# quadcopter.net
KiCad netlist of a schematic drawn in EAGLE
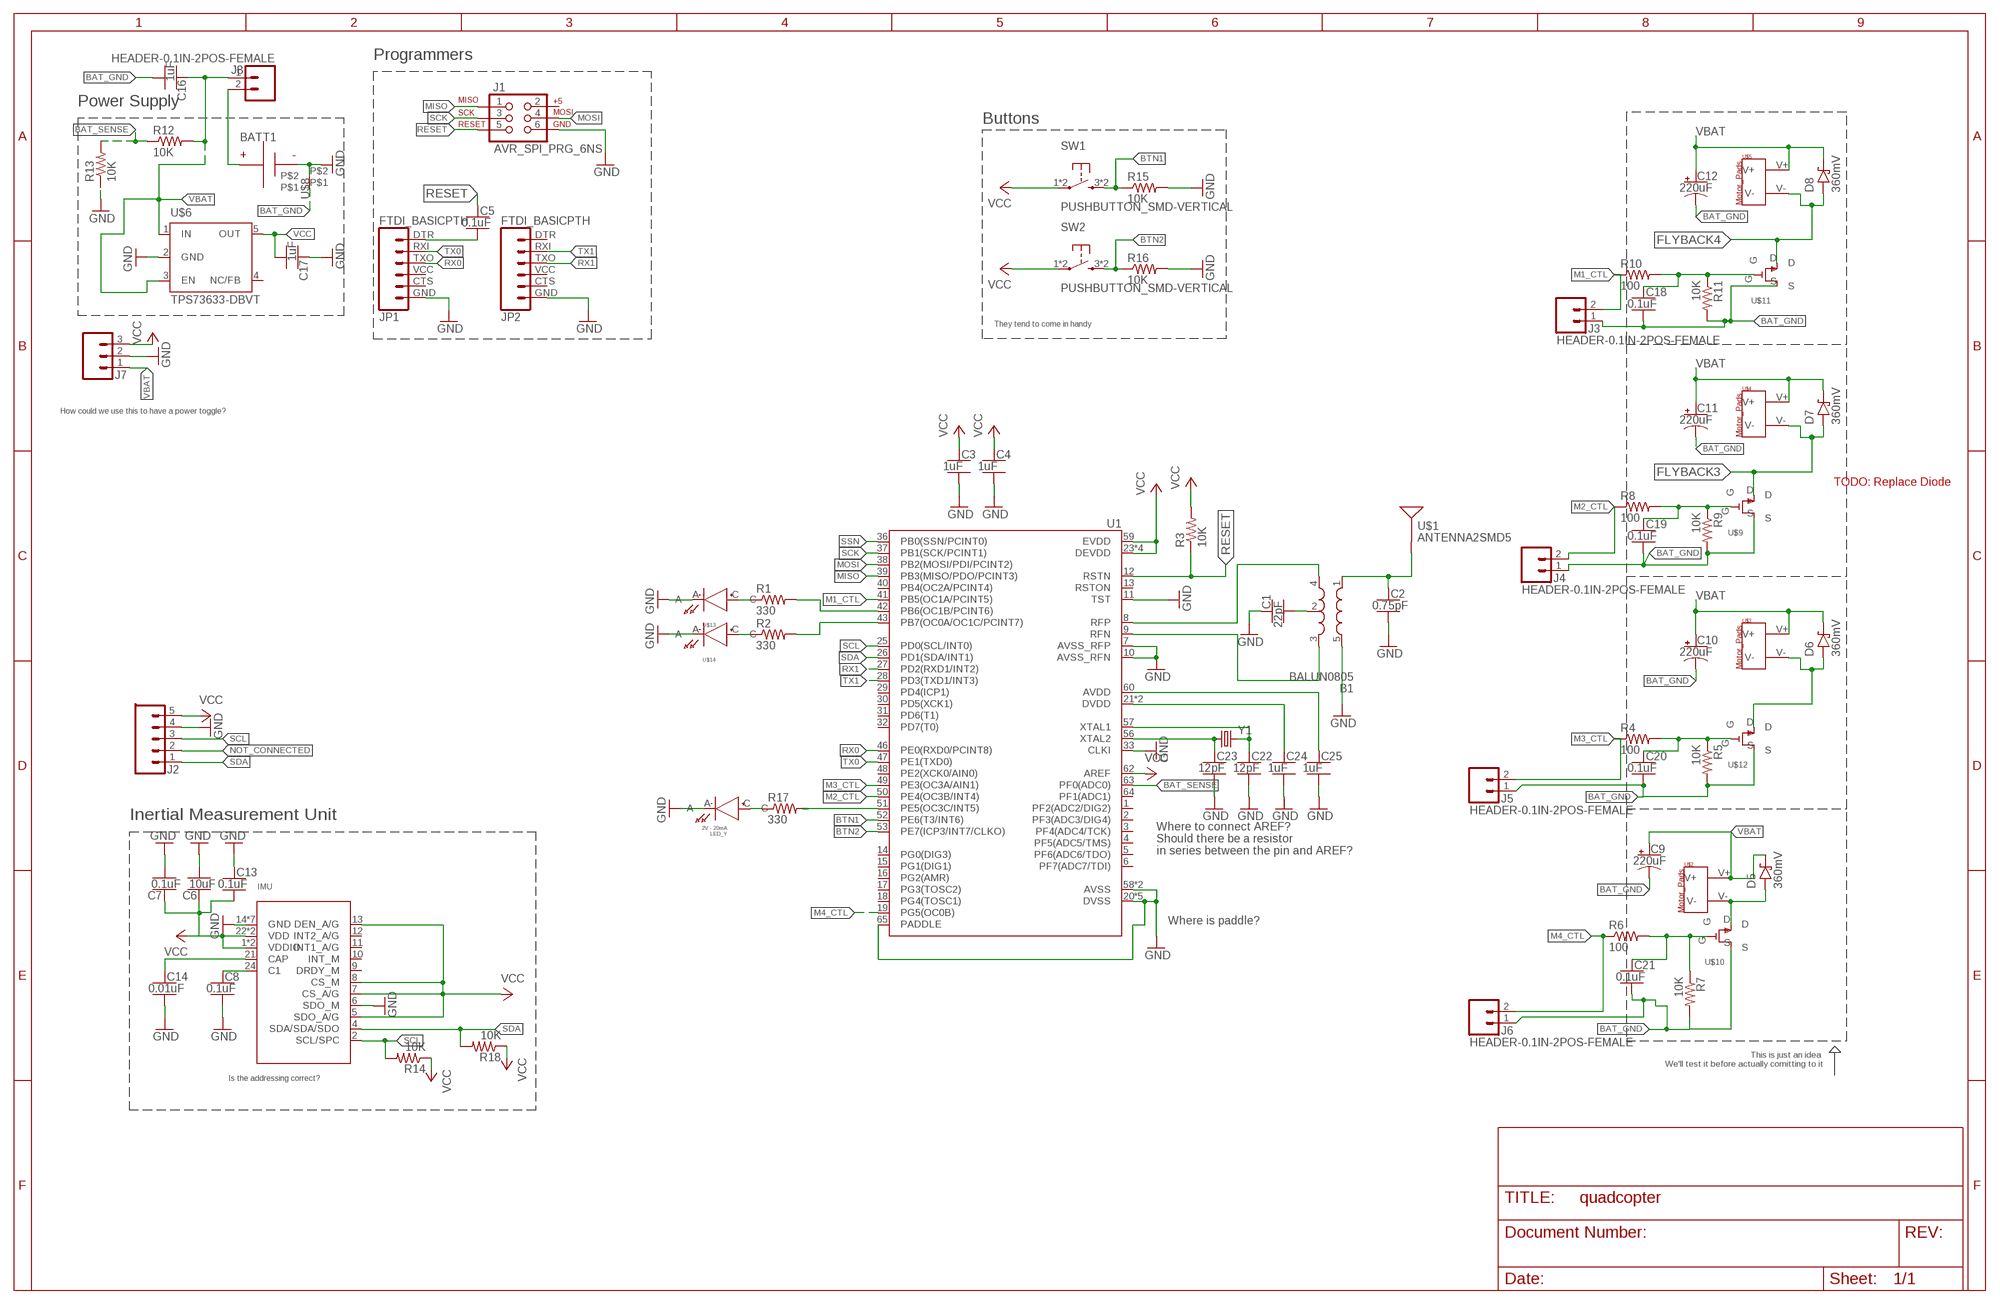
[diagram p0: schematic, sheet 1]

(export (version "E")
  (design (tool "Eeschema 10.0.6"))
  (components
    (comp (ref "B1")
      (value "BALUN0805")
      (footprint "eagle-import:BALUN")
      (fields (field (name "MFR") "Wurth Electronics Inc") (field (name "MPN") "748421245"))
      (libsource (lib "eagle-import") (part "BALUN0805"))
    )
    (comp (ref "BATT1")
      (value "BATTERY-HUBSAN-W/HOLDER")
      (footprint "eagle-import:BATTERY-W_HOLDER-380MAH-HUBSAN")
      (fields
        (field (name "MFR") "HUBSAN")
        (field (name "MPN") "X4-H107C-8-in-1")
        (field (name "CREATOR") "Swanson")
      )
      (libsource (lib "eagle-import") (part "BATTERY-HUBSAN-W/HOLDER"))
    )
    (comp (ref "C1")
      (value "22pF")
      (footprint "eagle-import:CAPC2012X140_HS")
      (fields
        (field (name "MFR") "Murata Electronics North America")
        (field (name "MPN") "GRM21A5C2E220JW01D")
      )
      (libsource (lib "eagle-import") (part "CAPACITOR-NP_SMD-2012-0805_CERAMIC-22PF"))
    )
    (comp (ref "C2")
      (value "0.75pF")
      (footprint "eagle-import:CAPC2012X140_HS")
      (fields
        (field (name "MFR") "Murata Electronics North America")
        (field (name "MPN") "GQM2195C2AR75CB01D")
      )
      (libsource (lib "eagle-import") (part "CAPACITOR-NP_SMD-2012-0805_CERAMIC-0.75PF"))
    )
    (comp (ref "C3")
      (value "1uF")
      (footprint "eagle-import:CAPC2012X140_HS")
      (fields
        (field (name "MFR") "Murata Electronics North America")
        (field (name "MPN") "GRM21BR71H105KA12L")
      )
      (libsource (lib "eagle-import") (part "CAPACITOR-NP_SMD-2012-0805_CERAMIC-1UF"))
    )
    (comp (ref "C4")
      (value "1uF")
      (footprint "eagle-import:CAPC2012X140_HS")
      (fields
        (field (name "MFR") "Murata Electronics North America")
        (field (name "MPN") "GRM21BR71H105KA12L")
      )
      (libsource (lib "eagle-import") (part "CAPACITOR-NP_SMD-2012-0805_CERAMIC-1UF"))
    )
    (comp (ref "C5")
      (value "0.1uF")
      (footprint "eagle-import:CAPC2012X140_HS")
      (fields
        (field (name "MFR") "Murata Electronics North America")
        (field (name "MPN") "GRM21BR71H104KA01L")
      )
      (libsource (lib "eagle-import") (part "CAPACITOR-NP_SMD-2012-0805_CERAMIC-0.1UF"))
    )
    (comp (ref "C6")
      (value "10uF")
      (footprint "eagle-import:CAPC2012X140_HS")
      (fields
        (field (name "MFR") "Murata Electronics North America")
        (field (name "MPN") "GRM21BR61E106KA73L")
      )
      (libsource (lib "eagle-import") (part "CAPACITOR-NP_SMD-2012-0805_CERAMIC-10UF"))
    )
    (comp (ref "C7")
      (value "0.1uF")
      (footprint "eagle-import:CAPC2012X140_HS")
      (fields
        (field (name "MFR") "Murata Electronics North America")
        (field (name "MPN") "GRM21BR71H104KA01L")
      )
      (libsource (lib "eagle-import") (part "CAPACITOR-NP_SMD-2012-0805_CERAMIC-0.1UF"))
    )
    (comp (ref "C8")
      (value "0.1uF")
      (footprint "eagle-import:CAPC2012X140_HS")
      (fields
        (field (name "MFR") "Murata Electronics North America")
        (field (name "MPN") "GRM21BR71H104KA01L")
      )
      (libsource (lib "eagle-import") (part "CAPACITOR-NP_SMD-2012-0805_CERAMIC-0.1UF"))
    )
    (comp (ref "C9")
      (value "220uF")
      (footprint "eagle-import:CAPMP7343X310_HS")
      (fields (field (name "MFR") "AVX Corporation") (field (name "MPN") "TAJD227K006RNJ"))
      (libsource (lib "eagle-import") (part "CAPACITOR-POL_SMD-7043-D_TANTALUM-220UF"))
    )
    (comp (ref "C10")
      (value "220uF")
      (footprint "eagle-import:CAPMP7343X310_HS")
      (fields (field (name "MFR") "AVX Corporation") (field (name "MPN") "TAJD227K006RNJ"))
      (libsource (lib "eagle-import") (part "CAPACITOR-POL_SMD-7043-D_TANTALUM-220UF"))
    )
    (comp (ref "C11")
      (value "220uF")
      (footprint "eagle-import:CAPMP7343X310_HS")
      (fields (field (name "MFR") "AVX Corporation") (field (name "MPN") "TAJD227K006RNJ"))
      (libsource (lib "eagle-import") (part "CAPACITOR-POL_SMD-7043-D_TANTALUM-220UF"))
    )
    (comp (ref "C12")
      (value "220uF")
      (footprint "eagle-import:CAPMP7343X310_HS")
      (fields (field (name "MFR") "AVX Corporation") (field (name "MPN") "TAJD227K006RNJ"))
      (libsource (lib "eagle-import") (part "CAPACITOR-POL_SMD-7043-D_TANTALUM-220UF"))
    )
    (comp (ref "C13")
      (value "0.1uF")
      (footprint "eagle-import:CAPC2012X140_HS")
      (fields
        (field (name "MFR") "Murata Electronics North America")
        (field (name "MPN") "GRM21BR71H104KA01L")
      )
      (libsource (lib "eagle-import") (part "CAPACITOR-NP_SMD-2012-0805_CERAMIC-0.1UF"))
    )
    (comp (ref "C14")
      (value "0.01uF")
      (footprint "eagle-import:CAPC2012X140_HS")
      (fields
        (field (name "MFR") "Murata Electronics North America")
        (field (name "MPN") "GRM2195C1H103FA01D")
      )
      (libsource (lib "eagle-import") (part "CAPACITOR-NP_SMD-2012-0805_CERAMIC-0.01UF"))
    )
    (comp (ref "C16")
      (value "1uF")
      (footprint "eagle-import:CAPC2012X140_HS")
      (fields
        (field (name "MFR") "Murata Electronics North America")
        (field (name "MPN") "GRM21BR71H105KA12L")
      )
      (libsource (lib "eagle-import") (part "CAPACITOR-NP_SMD-2012-0805_CERAMIC-1UF"))
    )
    (comp (ref "C17")
      (value "1uF")
      (footprint "eagle-import:CAPC2012X140_HS")
      (fields
        (field (name "MFR") "Murata Electronics North America")
        (field (name "MPN") "GRM21BR71H105KA12L")
      )
      (libsource (lib "eagle-import") (part "CAPACITOR-NP_SMD-2012-0805_CERAMIC-1UF"))
    )
    (comp (ref "C18")
      (value "0.1uF")
      (footprint "eagle-import:CAPC2012X140_HS")
      (fields
        (field (name "MFR") "Murata Electronics North America")
        (field (name "MPN") "GRM21BR71H104KA01L")
      )
      (libsource (lib "eagle-import") (part "CAPACITOR-NP_SMD-2012-0805_CERAMIC-0.1UF"))
    )
    (comp (ref "C19")
      (value "0.1uF")
      (footprint "eagle-import:CAPC2012X140_HS")
      (fields
        (field (name "MFR") "Murata Electronics North America")
        (field (name "MPN") "GRM21BR71H104KA01L")
      )
      (libsource (lib "eagle-import") (part "CAPACITOR-NP_SMD-2012-0805_CERAMIC-0.1UF"))
    )
    (comp (ref "C20")
      (value "0.1uF")
      (footprint "eagle-import:CAPC2012X140_HS")
      (fields
        (field (name "MFR") "Murata Electronics North America")
        (field (name "MPN") "GRM21BR71H104KA01L")
      )
      (libsource (lib "eagle-import") (part "CAPACITOR-NP_SMD-2012-0805_CERAMIC-0.1UF"))
    )
    (comp (ref "C21")
      (value "0.1uF")
      (footprint "eagle-import:CAPC2012X140_HS")
      (fields
        (field (name "MFR") "Murata Electronics North America")
        (field (name "MPN") "GRM21BR71H104KA01L")
      )
      (libsource (lib "eagle-import") (part "CAPACITOR-NP_SMD-2012-0805_CERAMIC-0.1UF"))
    )
    (comp (ref "C22")
      (value "12pF")
      (footprint "eagle-import:CAPC2012X140_HS")
      (fields
        (field (name "MFR") "Murata Electronics North America")
        (field (name "MPN") "GRM21A5C2E120JW01D")
      )
      (libsource (lib "eagle-import") (part "CAPACITOR-NP_SMD-2012-0805_CERAMIC-12PF"))
    )
    (comp (ref "C23")
      (value "12pF")
      (footprint "eagle-import:CAPC2012X140_HS")
      (fields
        (field (name "MFR") "Murata Electronics North America")
        (field (name "MPN") "GRM21A5C2E120JW01D")
      )
      (libsource (lib "eagle-import") (part "CAPACITOR-NP_SMD-2012-0805_CERAMIC-12PF"))
    )
    (comp (ref "C24")
      (value "1uF")
      (footprint "eagle-import:CAPC2012X140_HS")
      (fields
        (field (name "MFR") "Murata Electronics North America")
        (field (name "MPN") "GRM21BR71H105KA12L")
      )
      (libsource (lib "eagle-import") (part "CAPACITOR-NP_SMD-2012-0805_CERAMIC-1UF"))
    )
    (comp (ref "C25")
      (value "1uF")
      (footprint "eagle-import:CAPC2012X140_HS")
      (fields
        (field (name "MFR") "Murata Electronics North America")
        (field (name "MPN") "GRM21BR71H105KA12L")
      )
      (libsource (lib "eagle-import") (part "CAPACITOR-NP_SMD-2012-0805_CERAMIC-1UF"))
    )
    (comp (ref "D5")
      (value "360mV")
      (footprint "eagle-import:SOD3716X135_HS")
      (fields
        (field (name "MFR") "Toshiba Semiconductor and Storage")
        (field (name "MPN") "CRS08(TE85L,Q,M)")
      )
      (libsource (lib "eagle-import") (part "DIODE-SCHOTTKY_SMD-SOD123-360MV"))
    )
    (comp (ref "D6")
      (value "360mV")
      (footprint "eagle-import:SOD3716X135_HS")
      (fields
        (field (name "MFR") "Toshiba Semiconductor and Storage")
        (field (name "MPN") "CRS08(TE85L,Q,M)")
      )
      (libsource (lib "eagle-import") (part "DIODE-SCHOTTKY_SMD-SOD123-360MV"))
    )
    (comp (ref "D7")
      (value "360mV")
      (footprint "eagle-import:SOD3716X135_HS")
      (fields
        (field (name "MFR") "Toshiba Semiconductor and Storage")
        (field (name "MPN") "CRS08(TE85L,Q,M)")
      )
      (libsource (lib "eagle-import") (part "DIODE-SCHOTTKY_SMD-SOD123-360MV"))
    )
    (comp (ref "D8")
      (value "360mV")
      (footprint "eagle-import:SOD3716X135_HS")
      (fields
        (field (name "MFR") "Toshiba Semiconductor and Storage")
        (field (name "MPN") "CRS08(TE85L,Q,M)")
      )
      (libsource (lib "eagle-import") (part "DIODE-SCHOTTKY_SMD-SOD123-360MV"))
    )
    (comp (ref "IMU")
      (value "IMU")
      (footprint "eagle-import:IMU_LSM9DS1TR")
      (fields
        (field (name "MFR") "STMicroelectronics ")
        (field (name "MPN") "LSM9DS1TR ")
        (field (name "CREATOR") "Michael M. Gonzalez")
      )
      (libsource (lib "eagle-import") (part "IMU"))
    )
    (comp (ref "J1")
      (value "AVR_SPI_PRG_6NS")
      (footprint "eagle-import:2X3-NS")
      (fields (field (name "MFR") "Amphenol FCI") (field (name "MPN") "67997-206HLF"))
      (libsource (lib "eagle-import") (part "AVR_SPI_PRG_6NS"))
    )
    (comp (ref "J2")
      (value "HEADER-0.1IN-5POS-FEMALE")
      (footprint "eagle-import:HDRV5W63P254_5X1_1270X254H838_HS")
      (libsource (lib "eagle-import") (part "HEADER-0.1IN-5POS-FEMALE"))
    )
    (comp (ref "J3")
      (value "HEADER-0.1IN-2POS-FEMALE")
      (footprint "eagle-import:HDRV2W63P254_2X1_508X254H838_HS")
      (libsource (lib "eagle-import") (part "HEADER-0.1IN-2POS-FEMALE"))
    )
    (comp (ref "J4")
      (value "HEADER-0.1IN-2POS-FEMALE")
      (footprint "eagle-import:HDRV2W63P254_2X1_508X254H838_HS")
      (libsource (lib "eagle-import") (part "HEADER-0.1IN-2POS-FEMALE"))
    )
    (comp (ref "J5")
      (value "HEADER-0.1IN-2POS-FEMALE")
      (footprint "eagle-import:HDRV2W63P254_2X1_508X254H838_HS")
      (libsource (lib "eagle-import") (part "HEADER-0.1IN-2POS-FEMALE"))
    )
    (comp (ref "J6")
      (value "HEADER-0.1IN-2POS-FEMALE")
      (footprint "eagle-import:HDRV2W63P254_2X1_508X254H838_HS")
      (libsource (lib "eagle-import") (part "HEADER-0.1IN-2POS-FEMALE"))
    )
    (comp (ref "J7")
      (value "HEADER-0.1IN-3POS-MALE")
      (footprint "eagle-import:HDRV3W63P254_3X1_762X254H838_HS")
      (libsource (lib "eagle-import") (part "HEADER-0.1IN-3POS-MALE"))
    )
    (comp (ref "J8")
      (value "HEADER-0.1IN-2POS-FEMALE")
      (footprint "eagle-import:HDRV2W63P254_2X1_508X254H838_HS")
      (libsource (lib "eagle-import") (part "HEADER-0.1IN-2POS-FEMALE"))
    )
    (comp (ref "JP1")
      (value "FTDI_BASICPTH")
      (footprint "eagle-import:FTDI_BASIC")
      (fields (field (name "MFR") "Amphenol FCI") (field (name "MPN") "68016-406HLF"))
      (libsource (lib "eagle-import") (part "FTDI_BASICPTH"))
    )
    (comp (ref "JP2")
      (value "FTDI_BASICPTH")
      (footprint "eagle-import:FTDI_BASIC")
      (fields (field (name "MFR") "Amphenol FCI") (field (name "MPN") "68016-406HLF"))
      (libsource (lib "eagle-import") (part "FTDI_BASICPTH"))
    )
    (comp (ref "LED_Y")
      (value "2V - 20mA")
      (footprint "eagle-import:LED_LTST-C170EKT")
      (fields
        (field (name "MFR") "Visual Communications Company - VCC")
        (field (name "MPN") "CMD17-21VYD/TR8")
        (field (name "CREATOR") "Michael M. Gonzalez")
      )
      (libsource (lib "eagle-import") (part "LEDCMD17"))
    )
    (comp (ref "R1")
      (value "330")
      (footprint "eagle-import:RESC2012X60_HS")
      (fields (field (name "MFR") "Yageo") (field (name "MPN") "RC0805JR-07330RL"))
      (libsource (lib "eagle-import") (part "RESISTOR_SMD-2012-0805-330"))
    )
    (comp (ref "R2")
      (value "330")
      (footprint "eagle-import:RESC2012X60_HS")
      (fields (field (name "MFR") "Yageo") (field (name "MPN") "RC0805JR-07330RL"))
      (libsource (lib "eagle-import") (part "RESISTOR_SMD-2012-0805-330"))
    )
    (comp (ref "R3")
      (value "10K")
      (footprint "eagle-import:RESC2012X60_HS")
      (fields (field (name "MFR") "Yageo") (field (name "MPN") "RC0805JR-0710KL"))
      (libsource (lib "eagle-import") (part "RESISTOR_SMD-2012-0805-10K"))
    )
    (comp (ref "R4")
      (value "100")
      (footprint "eagle-import:RESC2012X60_HS")
      (fields (field (name "MFR") "Yageo") (field (name "MPN") "RC0805JR-07100RL"))
      (libsource (lib "eagle-import") (part "RESISTOR_SMD-2012-0805-100"))
    )
    (comp (ref "R5")
      (value "10K")
      (footprint "eagle-import:RESC2012X60_HS")
      (fields (field (name "MFR") "Yageo") (field (name "MPN") "RC0805JR-0710KL"))
      (libsource (lib "eagle-import") (part "RESISTOR_SMD-2012-0805-10K"))
    )
    (comp (ref "R6")
      (value "100")
      (footprint "eagle-import:RESC2012X60_HS")
      (fields (field (name "MFR") "Yageo") (field (name "MPN") "RC0805JR-07100RL"))
      (libsource (lib "eagle-import") (part "RESISTOR_SMD-2012-0805-100"))
    )
    (comp (ref "R7")
      (value "10K")
      (footprint "eagle-import:RESC2012X60_HS")
      (fields (field (name "MFR") "Yageo") (field (name "MPN") "RC0805JR-0710KL"))
      (libsource (lib "eagle-import") (part "RESISTOR_SMD-2012-0805-10K"))
    )
    (comp (ref "R8")
      (value "100")
      (footprint "eagle-import:RESC2012X60_HS")
      (fields (field (name "MFR") "Yageo") (field (name "MPN") "RC0805JR-07100RL"))
      (libsource (lib "eagle-import") (part "RESISTOR_SMD-2012-0805-100"))
    )
    (comp (ref "R9")
      (value "10K")
      (footprint "eagle-import:RESC2012X60_HS")
      (fields (field (name "MFR") "Yageo") (field (name "MPN") "RC0805JR-0710KL"))
      (libsource (lib "eagle-import") (part "RESISTOR_SMD-2012-0805-10K"))
    )
    (comp (ref "R10")
      (value "100")
      (footprint "eagle-import:RESC2012X60_HS")
      (fields (field (name "MFR") "Yageo") (field (name "MPN") "RC0805JR-07100RL"))
      (libsource (lib "eagle-import") (part "RESISTOR_SMD-2012-0805-100"))
    )
    (comp (ref "R11")
      (value "10K")
      (footprint "eagle-import:RESC2012X60_HS")
      (fields (field (name "MFR") "Yageo") (field (name "MPN") "RC0805JR-0710KL"))
      (libsource (lib "eagle-import") (part "RESISTOR_SMD-2012-0805-10K"))
    )
    (comp (ref "R12")
      (value "10K")
      (footprint "eagle-import:RESC2012X60_HS")
      (fields (field (name "MFR") "Yageo") (field (name "MPN") "RC0805JR-0710KL"))
      (libsource (lib "eagle-import") (part "RESISTOR_SMD-2012-0805-10K"))
    )
    (comp (ref "R13")
      (value "10K")
      (footprint "eagle-import:RESC2012X60_HS")
      (fields (field (name "MFR") "Yageo") (field (name "MPN") "RC0805JR-0710KL"))
      (libsource (lib "eagle-import") (part "RESISTOR_SMD-2012-0805-10K"))
    )
    (comp (ref "R14")
      (value "10K")
      (footprint "eagle-import:RESC2012X60_HS")
      (fields (field (name "MFR") "Yageo") (field (name "MPN") "RC0805JR-0710KL"))
      (libsource (lib "eagle-import") (part "RESISTOR_SMD-2012-0805-10K"))
    )
    (comp (ref "R15")
      (value "10K")
      (footprint "eagle-import:RESC2012X60_HS")
      (fields (field (name "MFR") "Yageo") (field (name "MPN") "RC0805JR-0710KL"))
      (libsource (lib "eagle-import") (part "RESISTOR_SMD-2012-0805-10K"))
    )
    (comp (ref "R16")
      (value "10K")
      (footprint "eagle-import:RESC2012X60_HS")
      (fields (field (name "MFR") "Yageo") (field (name "MPN") "RC0805JR-0710KL"))
      (libsource (lib "eagle-import") (part "RESISTOR_SMD-2012-0805-10K"))
    )
    (comp (ref "R17")
      (value "330")
      (footprint "eagle-import:RESC2012X60_HS")
      (fields (field (name "MFR") "Yageo") (field (name "MPN") "RC0805JR-07330RL"))
      (libsource (lib "eagle-import") (part "RESISTOR_SMD-2012-0805-330"))
    )
    (comp (ref "R18")
      (value "10K")
      (footprint "eagle-import:RESC2012X60_HS")
      (fields (field (name "MFR") "Yageo") (field (name "MPN") "RC0805JR-0710KL"))
      (libsource (lib "eagle-import") (part "RESISTOR_SMD-2012-0805-10K"))
    )
    (comp (ref "SW1")
      (value "PUSHBUTTON_SMD-VERTICAL")
      (footprint "eagle-import:TE_FSM8JSMA_HS")
      (libsource (lib "eagle-import") (part "PUSHBUTTON_SMD-VERTICAL"))
    )
    (comp (ref "SW2")
      (value "PUSHBUTTON_SMD-VERTICAL")
      (footprint "eagle-import:TE_FSM8JSMA_HS")
      (libsource (lib "eagle-import") (part "PUSHBUTTON_SMD-VERTICAL"))
    )
    (comp (ref "U$1")
      (value "ANTENNA2SMD5")
      (footprint "eagle-import:ANTENNA-CHIP5")
      (fields (field (name "MFR") "Linx Technologies Inc.") (field (name "MPN") "ANT-2.45-CHP-T"))
      (libsource (lib "eagle-import") (part "ANTENNA2SMD5"))
    )
    (comp (ref "U$2")
      (value "MOTOR_PADS")
      (footprint "eagle-import:MOTOR_PADS")
      (fields (field (name "MFR") "NA"))
      (libsource (lib "eagle-import") (part "MOTOR_PADS"))
    )
    (comp (ref "U$3")
      (value "MOTOR_PADS")
      (footprint "eagle-import:MOTOR_PADS")
      (fields (field (name "MFR") "NA"))
      (libsource (lib "eagle-import") (part "MOTOR_PADS"))
    )
    (comp (ref "U$4")
      (value "MOTOR_PADS")
      (footprint "eagle-import:MOTOR_PADS")
      (fields (field (name "MFR") "NA"))
      (libsource (lib "eagle-import") (part "MOTOR_PADS"))
    )
    (comp (ref "U$5")
      (value "MOTOR_PADS")
      (footprint "eagle-import:MOTOR_PADS")
      (fields (field (name "MFR") "NA"))
      (libsource (lib "eagle-import") (part "MOTOR_PADS"))
    )
    (comp (ref "U$6")
      (value "TPS73633-DBVT")
      (footprint "eagle-import:SOT23-DBV")
      (fields (field (name "MFR") "Texas Instruments") (field (name "MPN") "LP3985IM5X-3.0/NOPB"))
      (libsource (lib "eagle-import") (part "TPS73633-DBVT"))
    )
    (comp (ref "U$8")
      (value "NET_BRIDGE")
      (footprint "eagle-import:NET_BRIDGE")
      (fields
        (field (name "MFR") "Digikey")
        (field (name "MPN") "0")
        (field (name "CREATOR") "Michael Gonzalez")
      )
      (libsource (lib "eagle-import") (part "NET_BRIDGE"))
    )
    (comp (ref "U$9")
      (value "N-FET")
      (footprint "eagle-import:N_FET_SI2302CDS-T1-E3CT-ND")
      (fields
        (field (name "MFR") "Vishay Siliconix ")
        (field (name "MPN") "SI2302CDS-T1-E3 ")
        (field (name "CREATOR") "Michael M. Gonzalez")
      )
      (libsource (lib "eagle-import") (part "N-FET"))
    )
    (comp (ref "U$10")
      (value "N-FET")
      (footprint "eagle-import:N_FET_SI2302CDS-T1-E3CT-ND")
      (fields
        (field (name "MFR") "Vishay Siliconix ")
        (field (name "MPN") "SI2302CDS-T1-E3 ")
        (field (name "CREATOR") "Michael M. Gonzalez")
      )
      (libsource (lib "eagle-import") (part "N-FET"))
    )
    (comp (ref "U$11")
      (value "N-FET")
      (footprint "eagle-import:N_FET_SI2302CDS-T1-E3CT-ND")
      (fields
        (field (name "MFR") "Vishay Siliconix ")
        (field (name "MPN") "SI2302CDS-T1-E3 ")
        (field (name "CREATOR") "Michael M. Gonzalez")
      )
      (libsource (lib "eagle-import") (part "N-FET"))
    )
    (comp (ref "U$12")
      (value "N-FET")
      (footprint "eagle-import:N_FET_SI2302CDS-T1-E3CT-ND")
      (fields
        (field (name "MFR") "Vishay Siliconix ")
        (field (name "MPN") "SI2302CDS-T1-E3 ")
        (field (name "CREATOR") "Michael M. Gonzalez")
      )
      (libsource (lib "eagle-import") (part "N-FET"))
    )
    (comp (ref "U$13")
      (value "LED-RED")
      (footprint "eagle-import:LED_LTST-C170EKT")
      (fields
        (field (name "MFR") "Lite-On Inc")
        (field (name "MPN") "LTST-C170EKT")
        (field (name "CREATOR") "Michael M. Gonzalez")
      )
      (libsource (lib "eagle-import") (part "LED-RED"))
    )
    (comp (ref "U$14")
      (value "LED-RED")
      (footprint "eagle-import:LED_LTST-C170EKT")
      (fields
        (field (name "MFR") "Lite-On Inc")
        (field (name "MPN") "LTST-C170EKT")
        (field (name "CREATOR") "Michael M. Gonzalez")
      )
      (libsource (lib "eagle-import") (part "LED-RED"))
    )
    (comp (ref "U1")
      (value "ATMEGA128RFA1")
      (footprint "eagle-import:QFN-64")
      (fields
        (field (name "MFR") "Atmel")
        (field (name "MPN") "ATMEGA128RFA1-ZUR00")
        (field (name "CREATOR") "Swanson")
      )
      (libsource (lib "eagle-import") (part "ATMEGA128RFA1"))
    )
    (comp (ref "Y1")
      (value "CRYSTAL5X3")
      (footprint "eagle-import:CRYSTAL-SMD-5X3")
      (fields (field (name "MFR") "Abracon LLC") (field (name "MPN") "ABM3B-16.000MHZ-B2-T"))
      (libsource (lib "eagle-import") (part "CRYSTAL5X3"))
    )
  )
  (nets
    (net (code "1") (name "BAT_GND") (class "Default")
      (node (ref "C10") (pin "2") (pinfunction "-_2") (pintype "passive"))
      (node (ref "C11") (pin "2") (pinfunction "-_2") (pintype "passive"))
      (node (ref "C12") (pin "2") (pinfunction "-_2") (pintype "passive"))
      (node (ref "C16") (pin "2") (pinfunction "2_2") (pintype "passive"))
      (node (ref "C18") (pin "2") (pinfunction "2_2") (pintype "passive"))
      (node (ref "C19") (pin "2") (pinfunction "2_2") (pintype "passive"))
      (node (ref "C20") (pin "2") (pinfunction "2_2") (pintype "passive"))
      (node (ref "C21") (pin "2") (pinfunction "2_2") (pintype "passive"))
      (node (ref "C9") (pin "2") (pinfunction "-_2") (pintype "passive"))
      (node (ref "J3") (pin "1") (pinfunction "1_1") (pintype "passive"))
      (node (ref "J4") (pin "1") (pinfunction "1_1") (pintype "passive"))
      (node (ref "J5") (pin "1") (pinfunction "1_1") (pintype "passive"))
      (node (ref "J6") (pin "1") (pinfunction "1_1") (pintype "passive"))
      (node (ref "R11") (pin "2") (pinfunction "2_2") (pintype "passive"))
      (node (ref "R5") (pin "2") (pinfunction "2_2") (pintype "passive"))
      (node (ref "R7") (pin "2") (pinfunction "2_2") (pintype "passive"))
      (node (ref "R9") (pin "2") (pinfunction "2_2") (pintype "passive"))
      (node (ref "U$10") (pin "S") (pinfunction "S_S") (pintype "bidirectional"))
      (node (ref "U$11") (pin "S") (pinfunction "S_S") (pintype "bidirectional"))
      (node (ref "U$12") (pin "S") (pinfunction "S_S") (pintype "bidirectional"))
      (node (ref "U$8") (pin "P$1") (pinfunction "P$1_P$1") (pintype "bidirectional"))
      (node (ref "U$9") (pin "S") (pinfunction "S_S") (pintype "bidirectional"))
    )
    (net (code "2") (name "BAT_SENSE") (class "Default")
      (node (ref "R12") (pin "1") (pinfunction "1_1") (pintype "passive"))
      (node (ref "R13") (pin "2") (pinfunction "2_2") (pintype "passive"))
      (node (ref "U1") (pin "63") (pinfunction "PF0(ADC0)_63") (pintype "bidirectional"))
    )
    (net (code "3") (name "BTN1") (class "Default")
      (node (ref "R15") (pin "1") (pinfunction "1_1") (pintype "passive"))
      (node (ref "SW1") (pin "3") (pinfunction "2_3") (pintype "passive"))
      (node (ref "SW1") (pin "4") (pinfunction "2_4") (pintype "passive"))
      (node (ref "U1") (pin "52") (pinfunction "PE6(T3/INT6)_52") (pintype "bidirectional"))
    )
    (net (code "4") (name "BTN2") (class "Default")
      (node (ref "R16") (pin "1") (pinfunction "1_1") (pintype "passive"))
      (node (ref "SW2") (pin "3") (pinfunction "2_3") (pintype "passive"))
      (node (ref "SW2") (pin "4") (pinfunction "2_4") (pintype "passive"))
      (node (ref "U1") (pin "53") (pinfunction "PE7(ICP3/INT7/CLKO)_53") (pintype "bidirectional"))
    )
    (net (code "5") (name "FLYBACK3") (class "Default")
      (node (ref "D7") (pin "A") (pinfunction "A_A") (pintype "passive"))
      (node (ref "U$4") (pin "V-") (pinfunction "V-_V-") (pintype "bidirectional"))
      (node (ref "U$9") (pin "D") (pinfunction "D_D") (pintype "bidirectional"))
    )
    (net (code "6") (name "FLYBACK4") (class "Default")
      (node (ref "D8") (pin "A") (pinfunction "A_A") (pintype "passive"))
      (node (ref "U$11") (pin "D") (pinfunction "D_D") (pintype "bidirectional"))
      (node (ref "U$5") (pin "V-") (pinfunction "V-_V-") (pintype "bidirectional"))
    )
    (net (code "7") (name "GND") (class "Default")
      (node (ref "B1") (pin "5") (pinfunction "GND_5") (pintype "bidirectional"))
      (node (ref "BATT1") (pin "-") (pinfunction "N_-") (pintype "bidirectional"))
      (node (ref "C1") (pin "1") (pinfunction "1_1") (pintype "passive"))
      (node (ref "C13") (pin "1") (pinfunction "1_1") (pintype "passive"))
      (node (ref "C14") (pin "2") (pinfunction "2_2") (pintype "passive"))
      (node (ref "C17") (pin "1") (pinfunction "1_1") (pintype "passive"))
      (node (ref "C2") (pin "2") (pinfunction "2_2") (pintype "passive"))
      (node (ref "C22") (pin "2") (pinfunction "2_2") (pintype "passive"))
      (node (ref "C23") (pin "2") (pinfunction "2_2") (pintype "passive"))
      (node (ref "C24") (pin "2") (pinfunction "2_2") (pintype "passive"))
      (node (ref "C25") (pin "2") (pinfunction "2_2") (pintype "passive"))
      (node (ref "C3") (pin "2") (pinfunction "2_2") (pintype "passive"))
      (node (ref "C4") (pin "2") (pinfunction "2_2") (pintype "passive"))
      (node (ref "C6") (pin "2") (pinfunction "2_2") (pintype "passive"))
      (node (ref "C7") (pin "2") (pinfunction "2_2") (pintype "passive"))
      (node (ref "C8") (pin "2") (pinfunction "2_2") (pintype "passive"))
      (node (ref "IMU") (pin "14") (pinfunction "GND_14") (pintype "bidirectional"))
      (node (ref "IMU") (pin "15") (pinfunction "GND_15") (pintype "bidirectional"))
      (node (ref "IMU") (pin "16") (pinfunction "GND_16") (pintype "bidirectional"))
      (node (ref "IMU") (pin "17") (pinfunction "GND_17") (pintype "bidirectional"))
      (node (ref "IMU") (pin "18") (pinfunction "GND_18") (pintype "bidirectional"))
      (node (ref "IMU") (pin "19") (pinfunction "GND_19") (pintype "bidirectional"))
      (node (ref "IMU") (pin "20") (pinfunction "GND_20") (pintype "bidirectional"))
      (node (ref "IMU") (pin "6") (pinfunction "SDO_M_6") (pintype "bidirectional"))
      (node (ref "J1") (pin "6") (pinfunction "6_6") (pintype "passive"))
      (node (ref "J2") (pin "4") (pinfunction "4_4") (pintype "passive"))
      (node (ref "J7") (pin "2") (pinfunction "2_2") (pintype "passive"))
      (node (ref "JP1") (pin "GND") (pinfunction "6_GND") (pintype "passive"))
      (node (ref "JP2") (pin "GND") (pinfunction "6_GND") (pintype "passive"))
      (node (ref "LED_Y") (pin "A") (pinfunction "A_A") (pintype "bidirectional"))
      (node (ref "R13") (pin "1") (pinfunction "1_1") (pintype "passive"))
      (node (ref "R15") (pin "2") (pinfunction "2_2") (pintype "passive"))
      (node (ref "R16") (pin "2") (pinfunction "2_2") (pintype "passive"))
      (node (ref "U$13") (pin "A") (pinfunction "A_A") (pintype "bidirectional"))
      (node (ref "U$14") (pin "A") (pinfunction "A_A") (pintype "bidirectional"))
      (node (ref "U$6") (pin "2") (pinfunction "GND_2") (pintype "input"))
      (node (ref "U$8") (pin "P$2") (pinfunction "P$2_P$2") (pintype "bidirectional"))
      (node (ref "U1") (pin "10") (pinfunction "AVSS_RFN_10") (pintype "bidirectional"))
      (node (ref "U1") (pin "11") (pinfunction "TST_11") (pintype "bidirectional"))
      (node (ref "U1") (pin "20") (pinfunction "DVSS_20") (pintype "bidirectional"))
      (node (ref "U1") (pin "24") (pinfunction "DVSS_24") (pintype "bidirectional"))
      (node (ref "U1") (pin "33") (pinfunction "CLKI_33") (pintype "bidirectional"))
      (node (ref "U1") (pin "35") (pinfunction "DVSS_35") (pintype "bidirectional"))
      (node (ref "U1") (pin "45") (pinfunction "DVSS_45") (pintype "bidirectional"))
      (node (ref "U1") (pin "55") (pinfunction "DVSS_55") (pintype "bidirectional"))
      (node (ref "U1") (pin "58") (pinfunction "AVSS_58") (pintype "bidirectional"))
      (node (ref "U1") (pin "61") (pinfunction "AVSS_61") (pintype "bidirectional"))
      (node (ref "U1") (pin "65") (pinfunction "PADDLE_65") (pintype "bidirectional"))
      (node (ref "U1") (pin "7") (pinfunction "AVSS_RFP_7") (pintype "bidirectional"))
    )
    (net (code "8") (name "M1_CTL") (class "Default")
      (node (ref "J3") (pin "2") (pinfunction "2_2") (pintype "passive"))
      (node (ref "R10") (pin "1") (pinfunction "1_1") (pintype "passive"))
      (node (ref "U1") (pin "41") (pinfunction "PB5(OC1A/PCINT5)_41") (pintype "bidirectional"))
    )
    (net (code "9") (name "M2_CTL") (class "Default")
      (node (ref "J4") (pin "2") (pinfunction "2_2") (pintype "passive"))
      (node (ref "R8") (pin "1") (pinfunction "1_1") (pintype "passive"))
      (node (ref "U1") (pin "50") (pinfunction "PE4(OC3B/INT4)_50") (pintype "bidirectional"))
    )
    (net (code "10") (name "M3_CTL") (class "Default")
      (node (ref "J5") (pin "2") (pinfunction "2_2") (pintype "passive"))
      (node (ref "R4") (pin "1") (pinfunction "1_1") (pintype "passive"))
      (node (ref "U1") (pin "49") (pinfunction "PE3(OC3A/AIN1)_49") (pintype "bidirectional"))
    )
    (net (code "11") (name "M4_CTL") (class "Default")
      (node (ref "J6") (pin "2") (pinfunction "2_2") (pintype "passive"))
      (node (ref "R6") (pin "1") (pinfunction "1_1") (pintype "passive"))
      (node (ref "U1") (pin "19") (pinfunction "PG5(OC0B)_19") (pintype "bidirectional"))
    )
    (net (code "12") (name "MISO") (class "Default")
      (node (ref "J1") (pin "1") (pinfunction "1_1") (pintype "passive"))
      (node (ref "U1") (pin "39") (pinfunction "PB3(MISO/PDO/PCINT3)_39") (pintype "bidirectional"))
    )
    (net (code "13") (name "MOSI") (class "Default")
      (node (ref "J1") (pin "4") (pinfunction "4_4") (pintype "passive"))
      (node (ref "U1") (pin "38") (pinfunction "PB2(MOSI/PDI/PCINT2)_38") (pintype "bidirectional"))
    )
    (net (code "14") (name "NOT_CONNECTED") (class "Default")
      (node (ref "J2") (pin "2") (pinfunction "2_2") (pintype "passive"))
    )
    (net (code "15") (name "Net-(B1-GND-Pad2)") (class "Default")
      (node (ref "B1") (pin "2") (pinfunction "GND_2") (pintype "bidirectional"))
      (node (ref "C1") (pin "2") (pinfunction "2_2") (pintype "passive"))
    )
    (net (code "16") (name "Net-(B1-IN)") (class "Default")
      (node (ref "B1") (pin "1") (pinfunction "IN_1") (pintype "bidirectional"))
      (node (ref "C2") (pin "1") (pinfunction "1_1") (pintype "passive"))
      (node (ref "U$1") (pin "FEED") (pinfunction "SIGNAL_FEED") (pintype "bidirectional"))
    )
    (net (code "17") (name "Net-(B1-OUT1)") (class "Default")
      (node (ref "B1") (pin "4") (pinfunction "OUT1_4") (pintype "bidirectional"))
      (node (ref "U1") (pin "8") (pinfunction "RFP_8") (pintype "bidirectional"))
    )
    (net (code "18") (name "Net-(B1-OUT2)") (class "Default")
      (node (ref "B1") (pin "3") (pinfunction "OUT2_3") (pintype "bidirectional"))
      (node (ref "U1") (pin "9") (pinfunction "RFN_9") (pintype "bidirectional"))
    )
    (net (code "19") (name "Net-(BATT1-P)") (class "Default")
      (node (ref "BATT1") (pin "+") (pinfunction "P_+") (pintype "bidirectional"))
      (node (ref "J8") (pin "2") (pinfunction "2_2") (pintype "passive"))
    )
    (net (code "20") (name "Net-(C18-Pad1)") (class "Default")
      (node (ref "C18") (pin "1") (pinfunction "1_1") (pintype "passive"))
      (node (ref "R10") (pin "2") (pinfunction "2_2") (pintype "passive"))
      (node (ref "R11") (pin "1") (pinfunction "1_1") (pintype "passive"))
      (node (ref "U$11") (pin "G") (pinfunction "G_G") (pintype "bidirectional"))
    )
    (net (code "21") (name "Net-(C19-Pad1)") (class "Default")
      (node (ref "C19") (pin "1") (pinfunction "1_1") (pintype "passive"))
      (node (ref "R8") (pin "2") (pinfunction "2_2") (pintype "passive"))
      (node (ref "R9") (pin "1") (pinfunction "1_1") (pintype "passive"))
      (node (ref "U$9") (pin "G") (pinfunction "G_G") (pintype "bidirectional"))
    )
    (net (code "22") (name "Net-(C20-Pad1)") (class "Default")
      (node (ref "C20") (pin "1") (pinfunction "1_1") (pintype "passive"))
      (node (ref "R4") (pin "2") (pinfunction "2_2") (pintype "passive"))
      (node (ref "R5") (pin "1") (pinfunction "1_1") (pintype "passive"))
      (node (ref "U$12") (pin "G") (pinfunction "G_G") (pintype "bidirectional"))
    )
    (net (code "23") (name "Net-(C21-Pad1)") (class "Default")
      (node (ref "C21") (pin "1") (pinfunction "1_1") (pintype "passive"))
      (node (ref "R6") (pin "2") (pinfunction "2_2") (pintype "passive"))
      (node (ref "R7") (pin "1") (pinfunction "1_1") (pintype "passive"))
      (node (ref "U$10") (pin "G") (pinfunction "G_G") (pintype "bidirectional"))
    )
    (net (code "24") (name "Net-(C24-Pad1)") (class "Default")
      (node (ref "C24") (pin "1") (pinfunction "1_1") (pintype "passive"))
      (node (ref "U1") (pin "21") (pinfunction "DVDD_21") (pintype "bidirectional"))
      (node (ref "U1") (pin "22") (pinfunction "DVDD_22") (pintype "bidirectional"))
    )
    (net (code "25") (name "Net-(D5-PadA)") (class "Default")
      (node (ref "D5") (pin "A") (pinfunction "A_A") (pintype "passive"))
      (node (ref "U$10") (pin "D") (pinfunction "D_D") (pintype "bidirectional"))
      (node (ref "U$2") (pin "V-") (pinfunction "V-_V-") (pintype "bidirectional"))
    )
    (net (code "26") (name "Net-(D6-PadA)") (class "Default")
      (node (ref "D6") (pin "A") (pinfunction "A_A") (pintype "passive"))
      (node (ref "U$12") (pin "D") (pinfunction "D_D") (pintype "bidirectional"))
      (node (ref "U$3") (pin "V-") (pinfunction "V-_V-") (pintype "bidirectional"))
    )
    (net (code "27") (name "Net-(IMU-C1)") (class "Default")
      (node (ref "C8") (pin "1") (pinfunction "1_1") (pintype "passive"))
      (node (ref "IMU") (pin "24") (pinfunction "C1_24") (pintype "bidirectional"))
    )
    (net (code "28") (name "Net-(IMU-CAP)") (class "Default")
      (node (ref "C14") (pin "1") (pinfunction "1_1") (pintype "passive"))
      (node (ref "IMU") (pin "21") (pinfunction "CAP_21") (pintype "bidirectional"))
    )
    (net (code "29") (name "Net-(JP1-1)") (class "Default")
      (node (ref "C5") (pin "2") (pinfunction "2_2") (pintype "passive"))
      (node (ref "JP1") (pin "DTR") (pinfunction "1_DTR") (pintype "passive"))
    )
    (net (code "30") (name "Net-(LED_Y-PadC)") (class "Default")
      (node (ref "LED_Y") (pin "C") (pinfunction "C_C") (pintype "bidirectional"))
      (node (ref "R17") (pin "1") (pinfunction "1_1") (pintype "passive"))
    )
    (net (code "31") (name "Net-(R1-Pad1)") (class "Default")
      (node (ref "R1") (pin "1") (pinfunction "1_1") (pintype "passive"))
      (node (ref "U$13") (pin "C") (pinfunction "C_C") (pintype "bidirectional"))
    )
    (net (code "32") (name "Net-(R2-Pad1)") (class "Default")
      (node (ref "R2") (pin "1") (pinfunction "1_1") (pintype "passive"))
      (node (ref "U$14") (pin "C") (pinfunction "C_C") (pintype "bidirectional"))
    )
    (net (code "33") (name "Net-(U1-AVDD)") (class "Default")
      (node (ref "C25") (pin "1") (pinfunction "1_1") (pintype "passive"))
      (node (ref "U1") (pin "60") (pinfunction "AVDD_60") (pintype "bidirectional"))
    )
    (net (code "34") (name "Net-(U1-PB6(OC1B{slash}PCINT6))") (class "Default")
      (node (ref "R1") (pin "2") (pinfunction "2_2") (pintype "passive"))
      (node (ref "U1") (pin "42") (pinfunction "PB6(OC1B/PCINT6)_42") (pintype "bidirectional"))
    )
    (net (code "35") (name "Net-(U1-PB7(OC0A{slash}OC1C{slash}PCINT7))") (class "Default")
      (node (ref "R2") (pin "2") (pinfunction "2_2") (pintype "passive"))
      (node (ref "U1") (pin "43") (pinfunction "PB7(OC0A/OC1C/PCINT7)_43") (pintype "bidirectional"))
    )
    (net (code "36") (name "Net-(U1-PE5(OC3C{slash}INT5))") (class "Default")
      (node (ref "R17") (pin "2") (pinfunction "2_2") (pintype "passive"))
      (node (ref "U1") (pin "51") (pinfunction "PE5(OC3C/INT5)_51") (pintype "bidirectional"))
    )
    (net (code "37") (name "Net-(U1-XTAL1)") (class "Default")
      (node (ref "C22") (pin "1") (pinfunction "1_1") (pintype "passive"))
      (node (ref "U1") (pin "57") (pinfunction "XTAL1_57") (pintype "bidirectional"))
      (node (ref "Y1") (pin "3") (pinfunction "2_3") (pintype "passive"))
    )
    (net (code "38") (name "Net-(U1-XTAL2)") (class "Default")
      (node (ref "C23") (pin "1") (pinfunction "1_1") (pintype "passive"))
      (node (ref "U1") (pin "56") (pinfunction "XTAL2_56") (pintype "bidirectional"))
      (node (ref "Y1") (pin "1") (pinfunction "1_1") (pintype "passive"))
    )
    (net (code "39") (name "RESET") (class "Default")
      (node (ref "C5") (pin "1") (pinfunction "1_1") (pintype "passive"))
      (node (ref "J1") (pin "5") (pinfunction "5_5") (pintype "passive"))
      (node (ref "R3") (pin "1") (pinfunction "1_1") (pintype "passive"))
      (node (ref "U1") (pin "12") (pinfunction "RSTN_12") (pintype "bidirectional"))
    )
    (net (code "40") (name "RX0") (class "Default")
      (node (ref "JP1") (pin "TXO") (pinfunction "3_TXO") (pintype "passive"))
      (node (ref "U1") (pin "46") (pinfunction "PE0(RXD0/PCINT8)_46") (pintype "bidirectional"))
    )
    (net (code "41") (name "RX1") (class "Default")
      (node (ref "JP2") (pin "TXO") (pinfunction "3_TXO") (pintype "passive"))
      (node (ref "U1") (pin "27") (pinfunction "PD2(RXD1/INT2)_27") (pintype "bidirectional"))
    )
    (net (code "42") (name "SCK") (class "Default")
      (node (ref "J1") (pin "3") (pinfunction "3_3") (pintype "passive"))
      (node (ref "U1") (pin "37") (pinfunction "PB1(SCK/PCINT1)_37") (pintype "bidirectional"))
    )
    (net (code "43") (name "SCL") (class "Default")
      (node (ref "IMU") (pin "2") (pinfunction "SCL/SPC_2") (pintype "bidirectional"))
      (node (ref "J2") (pin "3") (pinfunction "3_3") (pintype "passive"))
      (node (ref "R14") (pin "2") (pinfunction "2_2") (pintype "passive"))
      (node (ref "U1") (pin "25") (pinfunction "PD0(SCL/INT0)_25") (pintype "bidirectional"))
    )
    (net (code "44") (name "SDA") (class "Default")
      (node (ref "IMU") (pin "4") (pinfunction "SDA/SDA/SDO_4") (pintype "bidirectional"))
      (node (ref "J2") (pin "1") (pinfunction "1_1") (pintype "passive"))
      (node (ref "R18") (pin "2") (pinfunction "2_2") (pintype "passive"))
      (node (ref "U1") (pin "26") (pinfunction "PD1(SDA/INT1)_26") (pintype "bidirectional"))
    )
    (net (code "45") (name "SSN") (class "Default")
      (node (ref "U1") (pin "36") (pinfunction "PB0(SSN/PCINT0)_36") (pintype "bidirectional"))
    )
    (net (code "46") (name "TX0") (class "Default")
      (node (ref "JP1") (pin "RXI") (pinfunction "2_RXI") (pintype "passive"))
      (node (ref "U1") (pin "47") (pinfunction "PE1(TXD0)_47") (pintype "bidirectional"))
    )
    (net (code "47") (name "TX1") (class "Default")
      (node (ref "JP2") (pin "RXI") (pinfunction "2_RXI") (pintype "passive"))
      (node (ref "U1") (pin "28") (pinfunction "PD3(TXD1/INT3)_28") (pintype "bidirectional"))
    )
    (net (code "48") (name "VBAT") (class "Default")
      (node (ref "C10") (pin "1") (pinfunction "+_1") (pintype "passive"))
      (node (ref "C11") (pin "1") (pinfunction "+_1") (pintype "passive"))
      (node (ref "C12") (pin "1") (pinfunction "+_1") (pintype "passive"))
      (node (ref "C16") (pin "1") (pinfunction "1_1") (pintype "passive"))
      (node (ref "C9") (pin "1") (pinfunction "+_1") (pintype "passive"))
      (node (ref "D5") (pin "C") (pinfunction "C_C") (pintype "passive"))
      (node (ref "D6") (pin "C") (pinfunction "C_C") (pintype "passive"))
      (node (ref "D7") (pin "C") (pinfunction "C_C") (pintype "passive"))
      (node (ref "D8") (pin "C") (pinfunction "C_C") (pintype "passive"))
      (node (ref "J7") (pin "1") (pinfunction "1_1") (pintype "passive"))
      (node (ref "J8") (pin "1") (pinfunction "1_1") (pintype "passive"))
      (node (ref "R12") (pin "2") (pinfunction "2_2") (pintype "passive"))
      (node (ref "U$2") (pin "V+") (pinfunction "V+_V+") (pintype "bidirectional"))
      (node (ref "U$3") (pin "V+") (pinfunction "V+_V+") (pintype "bidirectional"))
      (node (ref "U$4") (pin "V+") (pinfunction "V+_V+") (pintype "bidirectional"))
      (node (ref "U$5") (pin "V+") (pinfunction "V+_V+") (pintype "bidirectional"))
      (node (ref "U$6") (pin "1") (pinfunction "IN_1") (pintype "input"))
      (node (ref "U$6") (pin "3") (pinfunction "EN_3") (pintype "input"))
    )
    (net (code "49") (name "VCC") (class "Default")
      (node (ref "C13") (pin "2") (pinfunction "2_2") (pintype "passive"))
      (node (ref "C17") (pin "2") (pinfunction "2_2") (pintype "passive"))
      (node (ref "C3") (pin "1") (pinfunction "1_1") (pintype "passive"))
      (node (ref "C4") (pin "1") (pinfunction "1_1") (pintype "passive"))
      (node (ref "C6") (pin "1") (pinfunction "1_1") (pintype "passive"))
      (node (ref "C7") (pin "1") (pinfunction "1_1") (pintype "passive"))
      (node (ref "IMU") (pin "1") (pinfunction "VDDIO_1") (pintype "bidirectional"))
      (node (ref "IMU") (pin "13") (pinfunction "DEN_A/G_13") (pintype "bidirectional"))
      (node (ref "IMU") (pin "22") (pinfunction "VDD_22") (pintype "bidirectional"))
      (node (ref "IMU") (pin "23") (pinfunction "VDD_23") (pintype "bidirectional"))
      (node (ref "IMU") (pin "3") (pinfunction "VDDIO_3") (pintype "bidirectional"))
      (node (ref "IMU") (pin "5") (pinfunction "SDO_A/G_5") (pintype "bidirectional"))
      (node (ref "IMU") (pin "7") (pinfunction "CS_A/G_7") (pintype "bidirectional"))
      (node (ref "IMU") (pin "8") (pinfunction "CS_M_8") (pintype "bidirectional"))
      (node (ref "J2") (pin "5") (pinfunction "5_5") (pintype "passive"))
      (node (ref "J7") (pin "3") (pinfunction "3_3") (pintype "passive"))
      (node (ref "R14") (pin "1") (pinfunction "1_1") (pintype "passive"))
      (node (ref "R18") (pin "1") (pinfunction "1_1") (pintype "passive"))
      (node (ref "R3") (pin "2") (pinfunction "2_2") (pintype "passive"))
      (node (ref "SW1") (pin "1") (pinfunction "1_1") (pintype "passive"))
      (node (ref "SW1") (pin "2") (pinfunction "1_2") (pintype "passive"))
      (node (ref "SW2") (pin "1") (pinfunction "1_1") (pintype "passive"))
      (node (ref "SW2") (pin "2") (pinfunction "1_2") (pintype "passive"))
      (node (ref "U$6") (pin "5") (pinfunction "OUT_5") (pintype "passive"))
      (node (ref "U1") (pin "23") (pinfunction "DEVDD_23") (pintype "bidirectional"))
      (node (ref "U1") (pin "34") (pinfunction "DEVDD_34") (pintype "bidirectional"))
      (node (ref "U1") (pin "44") (pinfunction "DEVDD_44") (pintype "bidirectional"))
      (node (ref "U1") (pin "54") (pinfunction "DEVDD_54") (pintype "bidirectional"))
      (node (ref "U1") (pin "59") (pinfunction "EVDD_59") (pintype "bidirectional"))
      (node (ref "U1") (pin "62") (pinfunction "AREF_62") (pintype "bidirectional"))
    )
    (net (code "50") (name "unconnected-(IMU-DRDY_M-Pad9)") (class "Default")
      (node (ref "IMU") (pin "9") (pinfunction "DRDY_M_9") (pintype "bidirectional"))
    )
    (net (code "51") (name "unconnected-(IMU-INT1_A{slash}G-Pad11)") (class "Default")
      (node (ref "IMU") (pin "11") (pinfunction "INT1_A/G_11") (pintype "bidirectional"))
    )
    (net (code "52") (name "unconnected-(IMU-INT2_A{slash}G-Pad12)") (class "Default")
      (node (ref "IMU") (pin "12") (pinfunction "INT2_A/G_12") (pintype "bidirectional"))
    )
    (net (code "53") (name "unconnected-(IMU-INT_M-Pad10)") (class "Default")
      (node (ref "IMU") (pin "10") (pinfunction "INT_M_10") (pintype "bidirectional"))
    )
    (net (code "54") (name "unconnected-(J1-Pad2)") (class "Default")
      (node (ref "J1") (pin "2") (pinfunction "2_2") (pintype "passive"))
    )
    (net (code "55") (name "unconnected-(JP1-4-PadVCC)") (class "Default")
      (node (ref "JP1") (pin "VCC") (pinfunction "4_VCC") (pintype "passive"))
    )
    (net (code "56") (name "unconnected-(JP1-5-PadCTS)") (class "Default")
      (node (ref "JP1") (pin "CTS") (pinfunction "5_CTS") (pintype "passive"))
    )
    (net (code "57") (name "unconnected-(JP2-1-PadDTR)") (class "Default")
      (node (ref "JP2") (pin "DTR") (pinfunction "1_DTR") (pintype "passive"))
    )
    (net (code "58") (name "unconnected-(JP2-4-PadVCC)") (class "Default")
      (node (ref "JP2") (pin "VCC") (pinfunction "4_VCC") (pintype "passive"))
    )
    (net (code "59") (name "unconnected-(JP2-5-PadCTS)") (class "Default")
      (node (ref "JP2") (pin "CTS") (pinfunction "5_CTS") (pintype "passive"))
    )
    (net (code "60") (name "unconnected-(U$6-NC{slash}FB-Pad4)") (class "Default")
      (node (ref "U$6") (pin "4") (pinfunction "NC/FB_4") (pintype "passive"))
    )
    (net (code "61") (name "unconnected-(U1-PB4(OC2A{slash}PCINT4)-Pad40)") (class "Default")
      (node (ref "U1") (pin "40") (pinfunction "PB4(OC2A/PCINT4)_40") (pintype "bidirectional"))
    )
    (net (code "62") (name "unconnected-(U1-PD4(ICP1)-Pad29)") (class "Default")
      (node (ref "U1") (pin "29") (pinfunction "PD4(ICP1)_29") (pintype "bidirectional"))
    )
    (net (code "63") (name "unconnected-(U1-PD5(XCK1)-Pad30)") (class "Default")
      (node (ref "U1") (pin "30") (pinfunction "PD5(XCK1)_30") (pintype "bidirectional"))
    )
    (net (code "64") (name "unconnected-(U1-PD6(T1)-Pad31)") (class "Default")
      (node (ref "U1") (pin "31") (pinfunction "PD6(T1)_31") (pintype "bidirectional"))
    )
    (net (code "65") (name "unconnected-(U1-PD7(T0)-Pad32)") (class "Default")
      (node (ref "U1") (pin "32") (pinfunction "PD7(T0)_32") (pintype "bidirectional"))
    )
    (net (code "66") (name "unconnected-(U1-PE2(XCK0{slash}AIN0)-Pad48)") (class "Default")
      (node (ref "U1") (pin "48") (pinfunction "PE2(XCK0/AIN0)_48") (pintype "bidirectional"))
    )
    (net (code "67") (name "unconnected-(U1-PF1(ADC1)-Pad64)") (class "Default")
      (node (ref "U1") (pin "64") (pinfunction "PF1(ADC1)_64") (pintype "bidirectional"))
    )
    (net (code "68") (name "unconnected-(U1-PF2(ADC2{slash}DIG2)-Pad1)") (class "Default")
      (node (ref "U1") (pin "1") (pinfunction "PF2(ADC2/DIG2)_1") (pintype "bidirectional"))
    )
    (net (code "69") (name "unconnected-(U1-PF3(ADC3{slash}DIG4)-Pad2)") (class "Default")
      (node (ref "U1") (pin "2") (pinfunction "PF3(ADC3/DIG4)_2") (pintype "bidirectional"))
    )
    (net (code "70") (name "unconnected-(U1-PF4(ADC4{slash}TCK)-Pad3)") (class "Default")
      (node (ref "U1") (pin "3") (pinfunction "PF4(ADC4/TCK)_3") (pintype "bidirectional"))
    )
    (net (code "71") (name "unconnected-(U1-PF5(ADC5{slash}TMS)-Pad4)") (class "Default")
      (node (ref "U1") (pin "4") (pinfunction "PF5(ADC5/TMS)_4") (pintype "bidirectional"))
    )
    (net (code "72") (name "unconnected-(U1-PF6(ADC6{slash}TDO)-Pad5)") (class "Default")
      (node (ref "U1") (pin "5") (pinfunction "PF6(ADC6/TDO)_5") (pintype "bidirectional"))
    )
    (net (code "73") (name "unconnected-(U1-PF7(ADC7{slash}TDI)-Pad6)") (class "Default")
      (node (ref "U1") (pin "6") (pinfunction "PF7(ADC7/TDI)_6") (pintype "bidirectional"))
    )
    (net (code "74") (name "unconnected-(U1-PG0(DIG3)-Pad14)") (class "Default")
      (node (ref "U1") (pin "14") (pinfunction "PG0(DIG3)_14") (pintype "bidirectional"))
    )
    (net (code "75") (name "unconnected-(U1-PG1(DIG1)-Pad15)") (class "Default")
      (node (ref "U1") (pin "15") (pinfunction "PG1(DIG1)_15") (pintype "bidirectional"))
    )
    (net (code "76") (name "unconnected-(U1-PG2(AMR)-Pad16)") (class "Default")
      (node (ref "U1") (pin "16") (pinfunction "PG2(AMR)_16") (pintype "bidirectional"))
    )
    (net (code "77") (name "unconnected-(U1-PG3(TOSC2)-Pad17)") (class "Default")
      (node (ref "U1") (pin "17") (pinfunction "PG3(TOSC2)_17") (pintype "bidirectional"))
    )
    (net (code "78") (name "unconnected-(U1-PG4(TOSC1)-Pad18)") (class "Default")
      (node (ref "U1") (pin "18") (pinfunction "PG4(TOSC1)_18") (pintype "bidirectional"))
    )
    (net (code "79") (name "unconnected-(U1-RSTON-Pad13)") (class "Default")
      (node (ref "U1") (pin "13") (pinfunction "RSTON_13") (pintype "bidirectional"))
    )
  )
)
